# PWM.net
KiCad netlist of a schematic drawn in EasyEDA Pro
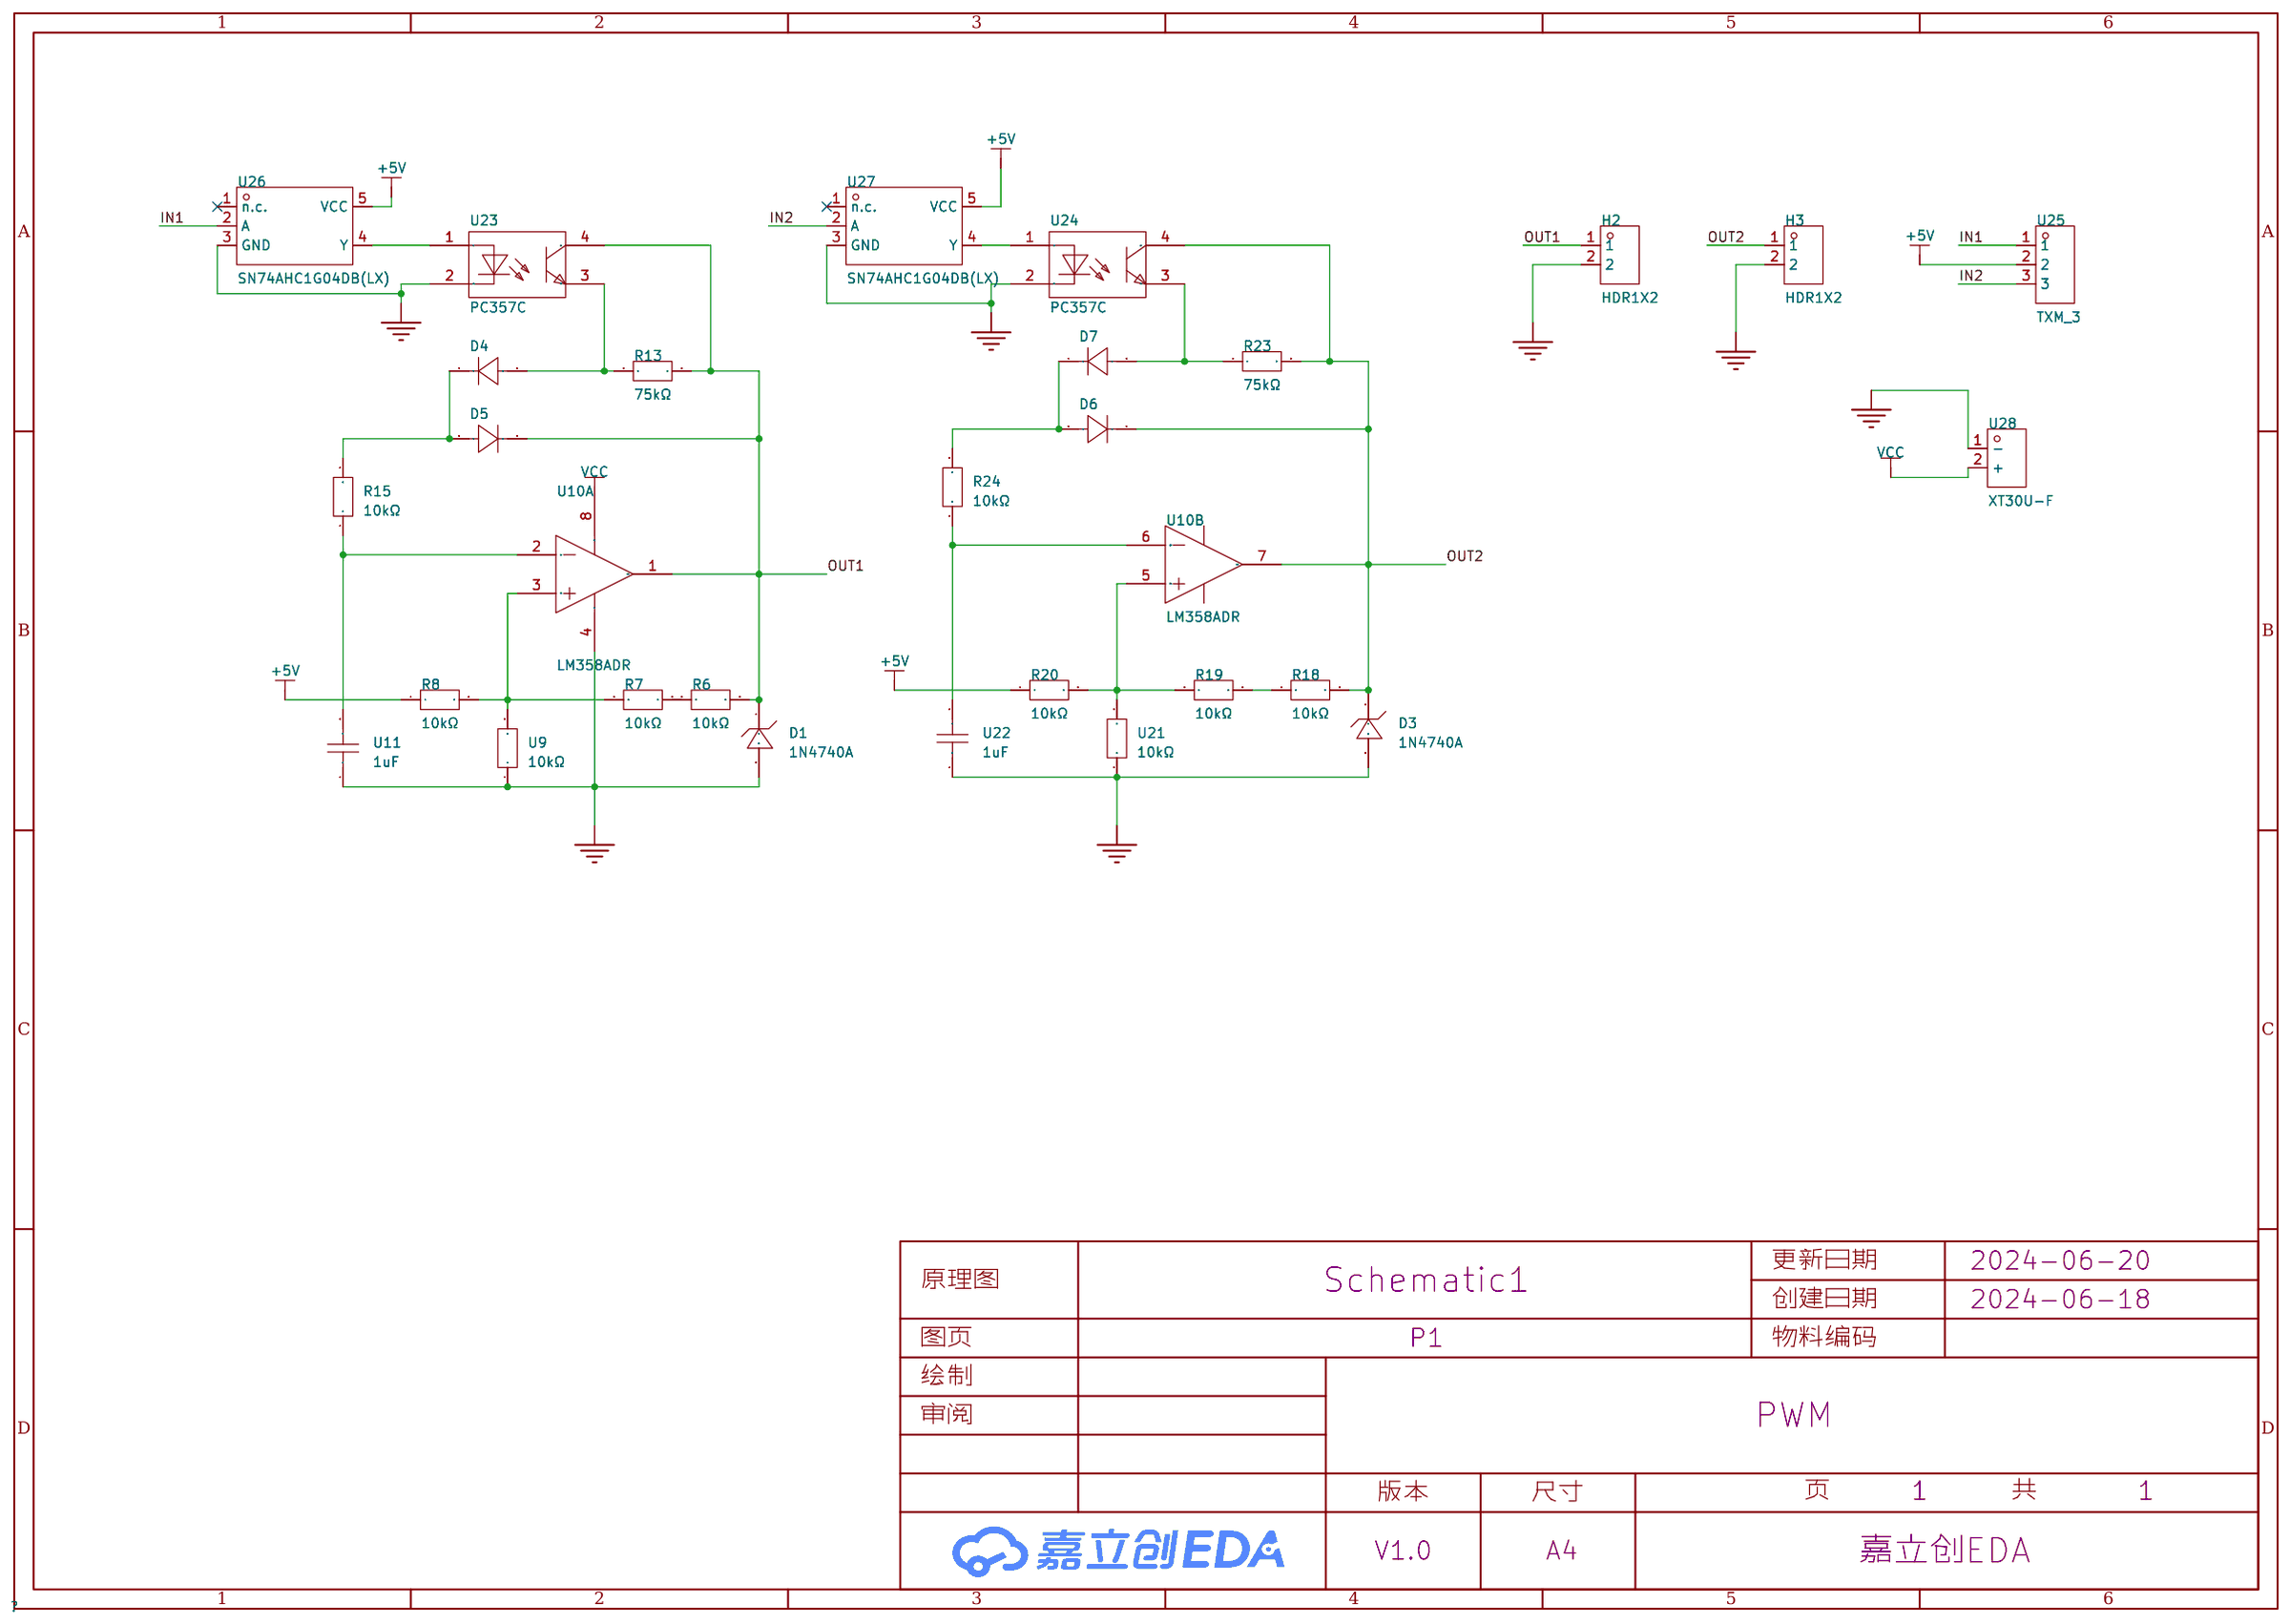
[diagram p0: schematic sheet]

(export (version "E")
  (design (tool "Eeschema 10.0.6"))
  (components
    (comp (ref "D1")
      (value "1N4740A")
      (footprint "easyedapro:DO-41_BD2.4-L4.7-P8.70-D0.9-RD")
      (description "二极管配置:独立式;稳压值(标称值):10V;功率(Pd):1W;")
      (fields (field (name "Manufacturer") "Multicomp"))
      (libsource (lib "easyedapro") (part "1N4740A_C194121"))
    )
    (comp (ref "D3")
      (value "1N4740A")
      (footprint "easyedapro:DO-41_BD2.4-L4.7-P8.70-D0.9-RD")
      (description "二极管配置:独立式;稳压值(标称值):10V;功率(Pd):1W;")
      (fields (field (name "Manufacturer") "Multicomp"))
      (libsource (lib "easyedapro") (part "1N4740A_C194121"))
    )
    (comp (ref "D4")
      (value "~")
      (footprint "easyedapro:SMA_1N4007")
      (libsource (lib "easyedapro") (part "D_1N4007"))
    )
    (comp (ref "D5")
      (value "~")
      (footprint "easyedapro:SMA_1N4007")
      (libsource (lib "easyedapro") (part "D_1N4007"))
    )
    (comp (ref "D6")
      (value "~")
      (footprint "easyedapro:SMA_1N4007")
      (libsource (lib "easyedapro") (part "D_1N4007"))
    )
    (comp (ref "D7")
      (value "~")
      (footprint "easyedapro:SMA_1N4007")
      (libsource (lib "easyedapro") (part "D_1N4007"))
    )
    (comp (ref "H2")
      (value "HDR1X2")
      (footprint "easyedapro:HDR-TH_2P-P2.54-V-M-1")
      (libsource (lib "easyedapro") (part "HDR1X2"))
    )
    (comp (ref "H3")
      (value "HDR1X2")
      (footprint "easyedapro:HDR-TH_2P-P2.54-V-M-1")
      (libsource (lib "easyedapro") (part "HDR1X2"))
    )
    (comp (ref "R6")
      (value "10kΩ")
      (footprint "easyedapro:R0603")
      (description "阻值:10kΩ;精度:±5%;功率:100mW;")
      (fields (field (name "Manufacturer Part") "RCA0310KJLF") (field (name "Manufacturer") "HKR(香港电阻)"))
      (libsource (lib "easyedapro") (part "RCA0310KJLF"))
    )
    (comp (ref "R7")
      (value "10kΩ")
      (footprint "easyedapro:R0603")
      (description "阻值:10kΩ;精度:±5%;功率:100mW;")
      (fields (field (name "Manufacturer Part") "RCA0310KJLF") (field (name "Manufacturer") "HKR(香港电阻)"))
      (libsource (lib "easyedapro") (part "RCA0310KJLF"))
    )
    (comp (ref "R8")
      (value "10kΩ")
      (footprint "easyedapro:R0603")
      (description "阻值:10kΩ;精度:±5%;功率:100mW;")
      (fields (field (name "Manufacturer Part") "RCA0310KJLF") (field (name "Manufacturer") "HKR(香港电阻)"))
      (libsource (lib "easyedapro") (part "RCA0310KJLF"))
    )
    (comp (ref "R13")
      (value "75kΩ")
      (footprint "easyedapro:R0805")
      (description "电阻类型:薄膜电阻;阻值:75kΩ;精度:±0.5%;功率:100mW;最大工作电压:100V;温度系数:±25ppm/°C;")
      (fields (field (name "Manufacturer Part") "WF08U7502DTL") (field (name "Manufacturer") "Walsin(华新科)"))
      (libsource (lib "easyedapro") (part "WF08U7502DTL"))
    )
    (comp (ref "R15")
      (value "10kΩ")
      (footprint "easyedapro:R0603")
      (description "阻值:10kΩ;精度:±5%;功率:100mW;")
      (fields (field (name "Manufacturer Part") "RCA0310KJLF") (field (name "Manufacturer") "HKR(香港电阻)"))
      (libsource (lib "easyedapro") (part "RCA0310KJLF"))
    )
    (comp (ref "R18")
      (value "10kΩ")
      (footprint "easyedapro:R0603")
      (description "阻值:10kΩ;精度:±5%;功率:100mW;")
      (fields (field (name "Manufacturer Part") "RCA0310KJLF") (field (name "Manufacturer") "HKR(香港电阻)"))
      (libsource (lib "easyedapro") (part "RCA0310KJLF"))
    )
    (comp (ref "R19")
      (value "10kΩ")
      (footprint "easyedapro:R0603")
      (description "阻值:10kΩ;精度:±5%;功率:100mW;")
      (fields (field (name "Manufacturer Part") "RCA0310KJLF") (field (name "Manufacturer") "HKR(香港电阻)"))
      (libsource (lib "easyedapro") (part "RCA0310KJLF"))
    )
    (comp (ref "R20")
      (value "10kΩ")
      (footprint "easyedapro:R0603")
      (description "阻值:10kΩ;精度:±5%;功率:100mW;")
      (fields (field (name "Manufacturer Part") "RCA0310KJLF") (field (name "Manufacturer") "HKR(香港电阻)"))
      (libsource (lib "easyedapro") (part "RCA0310KJLF"))
    )
    (comp (ref "R23")
      (value "75kΩ")
      (footprint "easyedapro:R0805")
      (description "电阻类型:薄膜电阻;阻值:75kΩ;精度:±0.5%;功率:100mW;最大工作电压:100V;温度系数:±25ppm/°C;")
      (fields (field (name "Manufacturer Part") "WF08U7502DTL") (field (name "Manufacturer") "Walsin(华新科)"))
      (libsource (lib "easyedapro") (part "WF08U7502DTL"))
    )
    (comp (ref "R24")
      (value "10kΩ")
      (footprint "easyedapro:R0603")
      (description "阻值:10kΩ;精度:±5%;功率:100mW;")
      (fields (field (name "Manufacturer Part") "RCA0310KJLF") (field (name "Manufacturer") "HKR(香港电阻)"))
      (libsource (lib "easyedapro") (part "RCA0310KJLF"))
    )
    (comp (ref "U9")
      (value "10kΩ")
      (footprint "easyedapro:R0603")
      (description "阻值:10kΩ;精度:±5%;功率:100mW;")
      (fields (field (name "Manufacturer Part") "RCA0310KJLF") (field (name "Manufacturer") "HKR(香港电阻)"))
      (libsource (lib "easyedapro") (part "RCA0310KJLF"))
    )
    (comp (ref "U10")
      (value "LM358ADR")
      (footprint "easyedapro:SOP-8_L4.9-W3.9-P1.27-LS6.0-BL")
      (description "放大器数:-;")
      (fields (field (name "Manufacturer") "UMW(友台半导体)"))
      (libsource (lib "easyedapro") (part "LM358ADR_C404320"))
    )
    (comp (ref "U11")
      (value "1uF")
      (footprint "easyedapro:C0603")
      (description "容值:1uF;精度:±10%;额定电压:25V;材质(温度系数):X5R;")
      (fields
        (field (name "Manufacturer Part") "HGC0603R5105K250NTHJ")
        (field (name "Manufacturer") "Chinocera(华瓷)")
      )
      (libsource (lib "easyedapro") (part "HGC0603R5105K250NTHJ"))
    )
    (comp (ref "U21")
      (value "10kΩ")
      (footprint "easyedapro:R0603")
      (description "阻值:10kΩ;精度:±5%;功率:100mW;")
      (fields (field (name "Manufacturer Part") "RCA0310KJLF") (field (name "Manufacturer") "HKR(香港电阻)"))
      (libsource (lib "easyedapro") (part "RCA0310KJLF"))
    )
    (comp (ref "U22")
      (value "1uF")
      (footprint "easyedapro:C0603")
      (description "容值:1uF;精度:±10%;额定电压:25V;材质(温度系数):X5R;")
      (fields
        (field (name "Manufacturer Part") "HGC0603R5105K250NTHJ")
        (field (name "Manufacturer") "Chinocera(华瓷)")
      )
      (libsource (lib "easyedapro") (part "HGC0603R5105K250NTHJ"))
    )
    (comp (ref "U23")
      (value "PC357C")
      (footprint "easyedapro:SOP-4_L4.6-W4.4-P2.54-LS7.0-TL")
      (fields (field (name "Manufacturer") "AOTE(奥特)"))
      (libsource (lib "easyedapro") (part "PC357C_C20612582"))
    )
    (comp (ref "U24")
      (value "PC357C")
      (footprint "easyedapro:SOP-4_L4.6-W4.4-P2.54-LS7.0-TL")
      (fields (field (name "Manufacturer") "AOTE(奥特)"))
      (libsource (lib "easyedapro") (part "PC357C_C20612582"))
    )
    (comp (ref "U25")
      (value "TXM_3")
      (footprint "easyedapro:HDR-TH_3P-P2.54-V-M-A")
      (libsource (lib "easyedapro") (part "TXM_3"))
    )
    (comp (ref "U26")
      (value "SN74AHC1G04DB(LX)")
      (footprint "easyedapro:SOT-23-5_L2.9-W1.6-P0.95-LS2.8-BR")
      (description "电源电压:2V~5.5V;供电电流(最大值):1uA;电路数:1;最大传播延迟(tpd):7.5ns@5.5V,50pF;")
      (fields (field (name "Manufacturer") "LX(灵星芯微)"))
      (libsource (lib "easyedapro") (part "SN74AHC1G04DB(LX)"))
    )
    (comp (ref "U27")
      (value "SN74AHC1G04DB(LX)")
      (footprint "easyedapro:SOT-23-5_L2.9-W1.6-P0.95-LS2.8-BR")
      (description "电源电压:2V~5.5V;供电电流(最大值):1uA;电路数:1;最大传播延迟(tpd):7.5ns@5.5V,50pF;")
      (fields (field (name "Manufacturer") "LX(灵星芯微)"))
      (libsource (lib "easyedapro") (part "SN74AHC1G04DB(LX)"))
    )
    (comp (ref "U28")
      (value "XT30U-F")
      (footprint "easyedapro:CONN-TH_XT30U-F")
      (description "类别:-;类型1:-;")
      (fields (field (name "Manufacturer") "AMASS(艾迈斯)"))
      (libsource (lib "easyedapro") (part "XT30U-F"))
    )
  )
  (nets
    (net (code "1") (name "+5V") (class "Default")
      (node (ref "R20") (pin "1") (pinfunction "1_1") (pintype "unspecified"))
      (node (ref "R8") (pin "1") (pinfunction "1_1") (pintype "unspecified"))
      (node (ref "U25") (pin "2") (pinfunction "2_2") (pintype "unspecified"))
      (node (ref "U26") (pin "5") (pinfunction "VCC_5") (pintype "unspecified"))
      (node (ref "U27") (pin "5") (pinfunction "VCC_5") (pintype "unspecified"))
    )
    (net (code "2") (name "/IN1") (class "Default")
      (node (ref "U25") (pin "1") (pinfunction "1_1") (pintype "unspecified"))
      (node (ref "U26") (pin "2") (pinfunction "A_2") (pintype "unspecified"))
    )
    (net (code "3") (name "/IN2") (class "Default")
      (node (ref "U25") (pin "3") (pinfunction "3_3") (pintype "unspecified"))
      (node (ref "U27") (pin "2") (pinfunction "A_2") (pintype "unspecified"))
    )
    (net (code "4") (name "/OUT1") (class "Default")
      (node (ref "D1") (pin "1") (pinfunction "1_1") (pintype "unspecified"))
      (node (ref "D5") (pin "1") (pinfunction "K_1") (pintype "input"))
      (node (ref "H2") (pin "1") (pinfunction "1_1") (pintype "unspecified"))
      (node (ref "R13") (pin "2") (pinfunction "2_2") (pintype "unspecified"))
      (node (ref "R6") (pin "2") (pinfunction "2_2") (pintype "unspecified"))
      (node (ref "U10") (pin "1") (pinfunction "OUT_A_1") (pintype "output"))
      (node (ref "U23") (pin "4") (pinfunction "COL_4") (pintype "unspecified"))
    )
    (net (code "5") (name "/OUT2") (class "Default")
      (node (ref "D3") (pin "1") (pinfunction "1_1") (pintype "unspecified"))
      (node (ref "D6") (pin "1") (pinfunction "K_1") (pintype "input"))
      (node (ref "H3") (pin "1") (pinfunction "1_1") (pintype "unspecified"))
      (node (ref "R18") (pin "2") (pinfunction "2_2") (pintype "unspecified"))
      (node (ref "R23") (pin "2") (pinfunction "2_2") (pintype "unspecified"))
      (node (ref "U10") (pin "7") (pinfunction "OUT_B_7") (pintype "output"))
      (node (ref "U24") (pin "4") (pinfunction "COL_4") (pintype "unspecified"))
    )
    (net (code "6") (name "GND") (class "Default")
      (node (ref "D1") (pin "2") (pinfunction "2_2") (pintype "unspecified"))
      (node (ref "D3") (pin "2") (pinfunction "2_2") (pintype "unspecified"))
      (node (ref "H2") (pin "2") (pinfunction "2_2") (pintype "unspecified"))
      (node (ref "H3") (pin "2") (pinfunction "2_2") (pintype "unspecified"))
      (node (ref "U10") (pin "4") (pinfunction "-V_4") (pintype "unspecified"))
      (node (ref "U11") (pin "1") (pinfunction "1_1") (pintype "unspecified"))
      (node (ref "U21") (pin "1") (pinfunction "1_1") (pintype "unspecified"))
      (node (ref "U22") (pin "1") (pinfunction "1_1") (pintype "unspecified"))
      (node (ref "U23") (pin "2") (pinfunction "CAT_2") (pintype "unspecified"))
      (node (ref "U24") (pin "2") (pinfunction "CAT_2") (pintype "unspecified"))
      (node (ref "U26") (pin "3") (pinfunction "GND_3") (pintype "unspecified"))
      (node (ref "U27") (pin "3") (pinfunction "GND_3") (pintype "unspecified"))
      (node (ref "U28") (pin "1") (pinfunction "-_1") (pintype "unspecified"))
      (node (ref "U9") (pin "1") (pinfunction "1_1") (pintype "unspecified"))
    )
    (net (code "7") (name "Net-(D4-A)") (class "Default")
      (node (ref "D4") (pin "2") (pinfunction "A_2") (pintype "input"))
      (node (ref "R13") (pin "1") (pinfunction "1_1") (pintype "unspecified"))
      (node (ref "U23") (pin "3") (pinfunction "EM_3") (pintype "unspecified"))
    )
    (net (code "8") (name "Net-(D4-K)") (class "Default")
      (node (ref "D4") (pin "1") (pinfunction "K_1") (pintype "input"))
      (node (ref "D5") (pin "2") (pinfunction "A_2") (pintype "input"))
      (node (ref "R15") (pin "2") (pinfunction "2_2") (pintype "unspecified"))
    )
    (net (code "9") (name "Net-(D6-A)") (class "Default")
      (node (ref "D6") (pin "2") (pinfunction "A_2") (pintype "input"))
      (node (ref "D7") (pin "1") (pinfunction "K_1") (pintype "input"))
      (node (ref "R24") (pin "2") (pinfunction "2_2") (pintype "unspecified"))
    )
    (net (code "10") (name "Net-(D7-A)") (class "Default")
      (node (ref "D7") (pin "2") (pinfunction "A_2") (pintype "input"))
      (node (ref "R23") (pin "1") (pinfunction "1_1") (pintype "unspecified"))
      (node (ref "U24") (pin "3") (pinfunction "EM_3") (pintype "unspecified"))
    )
    (net (code "11") (name "Net-(R6-Pad1)") (class "Default")
      (node (ref "R6") (pin "1") (pinfunction "1_1") (pintype "unspecified"))
      (node (ref "R7") (pin "2") (pinfunction "2_2") (pintype "unspecified"))
    )
    (net (code "12") (name "Net-(R18-Pad1)") (class "Default")
      (node (ref "R18") (pin "1") (pinfunction "1_1") (pintype "unspecified"))
      (node (ref "R19") (pin "2") (pinfunction "2_2") (pintype "unspecified"))
    )
    (net (code "13") (name "Net-(U10A-+IN_A)") (class "Default")
      (node (ref "R7") (pin "1") (pinfunction "1_1") (pintype "unspecified"))
      (node (ref "R8") (pin "2") (pinfunction "2_2") (pintype "unspecified"))
      (node (ref "U10") (pin "3") (pinfunction "+IN_A_3") (pintype "unspecified"))
      (node (ref "U9") (pin "2") (pinfunction "2_2") (pintype "unspecified"))
    )
    (net (code "14") (name "Net-(U10A--IN_A)") (class "Default")
      (node (ref "R15") (pin "1") (pinfunction "1_1") (pintype "unspecified"))
      (node (ref "U10") (pin "2") (pinfunction "-IN_A_2") (pintype "unspecified"))
      (node (ref "U11") (pin "2") (pinfunction "2_2") (pintype "unspecified"))
    )
    (net (code "15") (name "Net-(U10B-+IN_B)") (class "Default")
      (node (ref "R19") (pin "1") (pinfunction "1_1") (pintype "unspecified"))
      (node (ref "R20") (pin "2") (pinfunction "2_2") (pintype "unspecified"))
      (node (ref "U10") (pin "5") (pinfunction "+IN_B_5") (pintype "unspecified"))
      (node (ref "U21") (pin "2") (pinfunction "2_2") (pintype "unspecified"))
    )
    (net (code "16") (name "Net-(U10B--IN_B)") (class "Default")
      (node (ref "R24") (pin "1") (pinfunction "1_1") (pintype "unspecified"))
      (node (ref "U10") (pin "6") (pinfunction "-IN_B_6") (pintype "unspecified"))
      (node (ref "U22") (pin "2") (pinfunction "2_2") (pintype "unspecified"))
    )
    (net (code "17") (name "Net-(U23-AN)") (class "Default")
      (node (ref "U23") (pin "1") (pinfunction "AN_1") (pintype "unspecified"))
      (node (ref "U26") (pin "4") (pinfunction "Y_4") (pintype "unspecified"))
    )
    (net (code "18") (name "Net-(U24-AN)") (class "Default")
      (node (ref "U24") (pin "1") (pinfunction "AN_1") (pintype "unspecified"))
      (node (ref "U27") (pin "4") (pinfunction "Y_4") (pintype "unspecified"))
    )
    (net (code "19") (name "VCC") (class "Default")
      (node (ref "U10") (pin "8") (pinfunction "+V_8") (pintype "unspecified"))
      (node (ref "U28") (pin "2") (pinfunction "+_2") (pintype "unspecified"))
    )
    (net (code "20") (name "unconnected-(U26-n.c.-Pad1)") (class "Default")
      (node (ref "U26") (pin "1") (pinfunction "n.c._1") (pintype "unspecified+no_connect"))
    )
    (net (code "21") (name "unconnected-(U27-n.c.-Pad1)") (class "Default")
      (node (ref "U27") (pin "1") (pinfunction "n.c._1") (pintype "unspecified+no_connect"))
    )
  )
)
